# USB_Blaster.net
KiCad netlist of a schematic drawn in Altium Designer
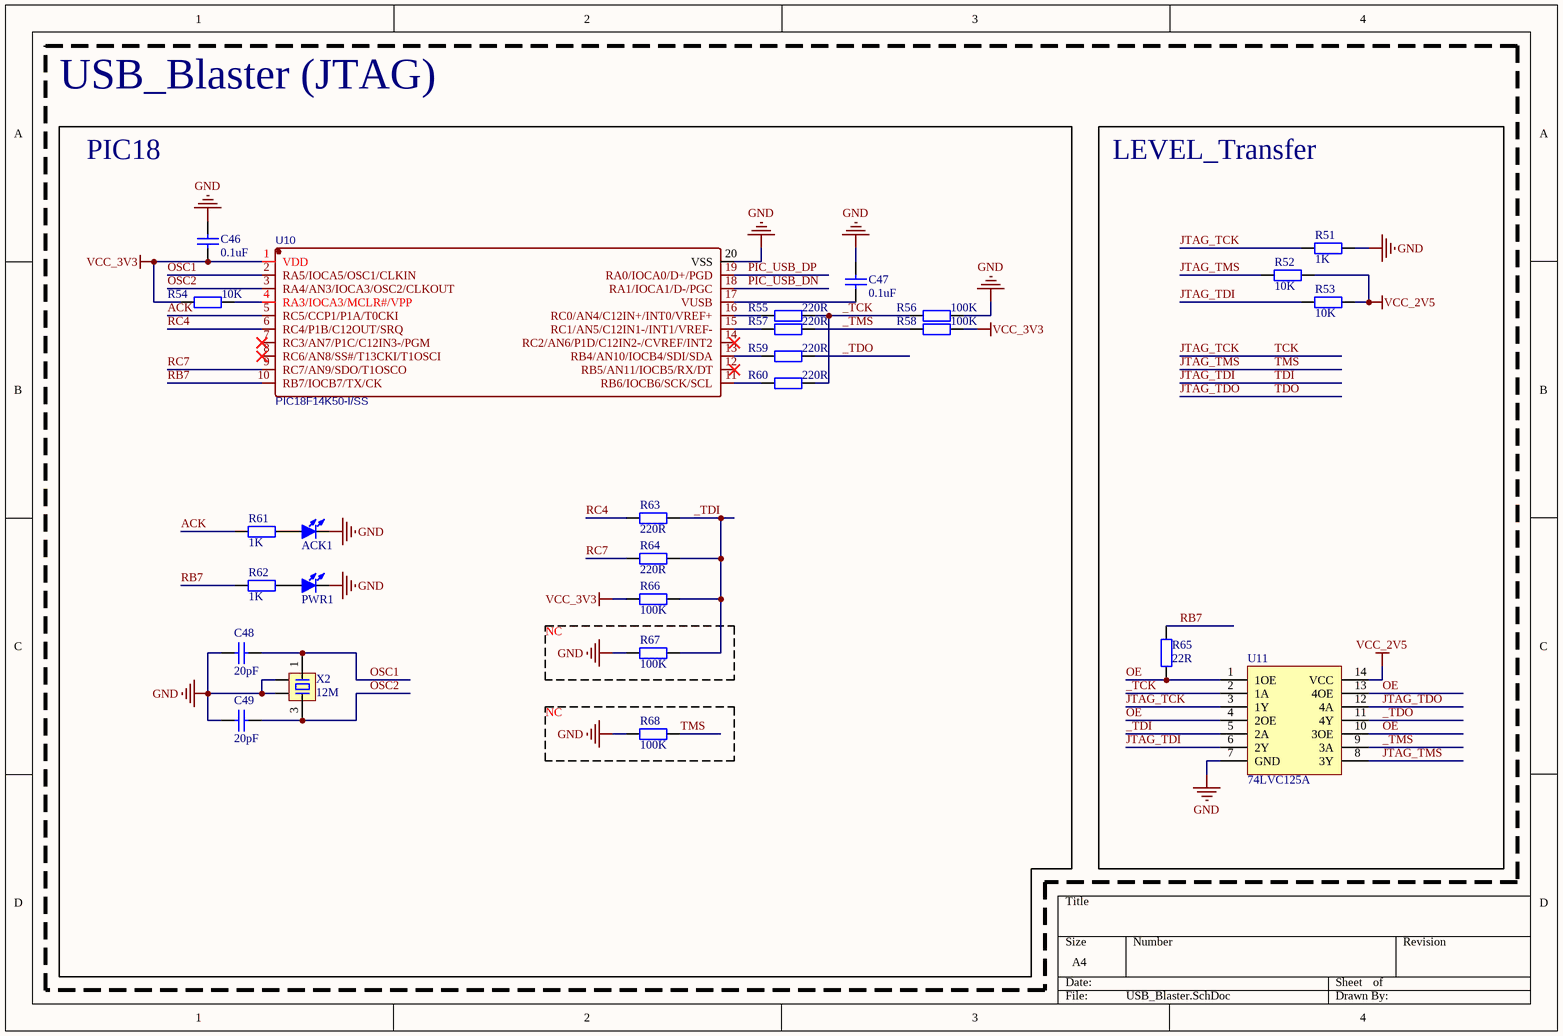
[diagram p0: USB_Blaster.SchDoc]

(export (version "E")
  (design (tool "Eeschema 10.0.6"))
  (components
    (comp (ref "ACK1")
      (value "红色")
      (footprint "LED 0603G")
      (description "贴片LED")
      (fields (field (name "版权归属") "源创客"))
      (libsource (lib "My_Devices") (part "0603_LED_G"))
    )
    (comp (ref "C46")
      (value "0.1uF")
      (footprint "0402_C")
      (description "贴片电容")
      (libsource (lib "My_Devices") (part "0402_C"))
    )
    (comp (ref "C47")
      (value "0.1uF")
      (footprint "0402_C")
      (description "贴片电容")
      (libsource (lib "My_Devices") (part "0402_C"))
    )
    (comp (ref "C48")
      (value "20pF")
      (footprint "0402_C")
      (description "贴片电容")
      (libsource (lib "My_Devices") (part "0402_C"))
    )
    (comp (ref "C49")
      (value "20pF")
      (footprint "0402_C")
      (description "贴片电容")
      (libsource (lib "My_Devices") (part "0402_C"))
    )
    (comp (ref "PWR1")
      (value "红色")
      (footprint "LED 0603R")
      (description "贴片LED")
      (fields (field (name "版权归属") "源创客"))
      (libsource (lib "My_Devices") (part "0603_LED_R"))
    )
    (comp (ref "R51")
      (value "1K")
      (footprint "0402_R")
      (description "贴片电阻")
      (libsource (lib "My_Devices") (part "0402_R"))
    )
    (comp (ref "R52")
      (value "10K")
      (footprint "0402_R")
      (description "贴片电阻")
      (libsource (lib "My_Devices") (part "0402_R"))
    )
    (comp (ref "R53")
      (value "10K")
      (footprint "0402_R")
      (description "贴片电阻")
      (libsource (lib "My_Devices") (part "0402_R"))
    )
    (comp (ref "R54")
      (value "10K")
      (footprint "0402_R")
      (description "贴片电阻")
      (libsource (lib "My_Devices") (part "0402_R"))
    )
    (comp (ref "R55")
      (value "220R")
      (footprint "0402_R")
      (description "贴片电阻")
      (libsource (lib "My_Devices") (part "0402_R"))
    )
    (comp (ref "R56")
      (value "100K")
      (footprint "0402_R")
      (description "贴片电阻")
      (libsource (lib "My_Devices") (part "0402_R"))
    )
    (comp (ref "R57")
      (value "220R")
      (footprint "0402_R")
      (description "贴片电阻")
      (libsource (lib "My_Devices") (part "0402_R"))
    )
    (comp (ref "R58")
      (value "100K")
      (footprint "0402_R")
      (description "贴片电阻")
      (libsource (lib "My_Devices") (part "0402_R"))
    )
    (comp (ref "R59")
      (value "220R")
      (footprint "0402_R")
      (description "贴片电阻")
      (libsource (lib "My_Devices") (part "0402_R"))
    )
    (comp (ref "R60")
      (value "220R")
      (footprint "0402_R")
      (description "贴片电阻")
      (libsource (lib "My_Devices") (part "0402_R"))
    )
    (comp (ref "R61")
      (value "1K")
      (footprint "0402_R")
      (description "贴片电阻")
      (libsource (lib "") (part "0402_R_1"))
    )
    (comp (ref "R62")
      (value "1K")
      (footprint "0402_R")
      (description "贴片电阻")
      (libsource (lib "") (part "0402_R_1"))
    )
    (comp (ref "R63")
      (value "220R")
      (footprint "0402_R")
      (description "贴片电阻")
      (libsource (lib "My_Devices") (part "0402_R"))
    )
    (comp (ref "R64")
      (value "220R")
      (footprint "0402_R")
      (description "贴片电阻")
      (libsource (lib "My_Devices") (part "0402_R"))
    )
    (comp (ref "R65")
      (value "22R")
      (footprint "0402_R")
      (description "贴片电阻")
      (libsource (lib "") (part "0402_R_2"))
    )
    (comp (ref "R66")
      (value "100K")
      (footprint "0402_R")
      (description "贴片电阻")
      (libsource (lib "") (part "0402_R_1"))
    )
    (comp (ref "R67")
      (value "100K")
      (footprint "0402_R")
      (description "贴片电阻")
      (libsource (lib "") (part "0402_R_1"))
    )
    (comp (ref "R68")
      (value "100K")
      (footprint "0402_R")
      (description "贴片电阻")
      (libsource (lib "") (part "0402_R_1"))
    )
    (comp (ref "U10")
      (value "PIC18F14K50-I/SS")
      (footprint "SSOP20_L")
      (fields (field (name "BOM_SUPPLIER PART") "C12460"))
      (libsource (lib "Schlib1") (part "PIC18F14K50-I/SS"))
    )
    (comp (ref "U11")
      (value "74LVC125A")
      (footprint "TSSOP14_N")
      (libsource (lib "Schlib1") (part "74LVC125A"))
    )
    (comp (ref "X2")
      (value "12M")
      (footprint "OSC 3225-4P")
      (description "4脚无源晶振")
      (fields (field (name "版权归属") "源创客"))
      (libsource (lib "My_Devices") (part "XTAL-4P"))
    )
  )
  (nets
    (net (code "1") (name "/ACK") (class "Default")
      (node (ref "R61") (pin "2") (pinfunction "2_2") (pintype "passive"))
      (node (ref "U10") (pin "5") (pinfunction "RC5/CCP1/P1A/T0CKI_5") (pintype "passive"))
    )
    (net (code "2") (name "/JTAG_TCK") (class "Default")
      (node (ref "R51") (pin "1") (pinfunction "1_1") (pintype "passive"))
      (node (ref "U11") (pin "3") (pinfunction "1Y_3") (pintype "passive"))
    )
    (net (code "3") (name "/JTAG_TDI") (class "Default")
      (node (ref "R53") (pin "1") (pinfunction "1_1") (pintype "passive"))
      (node (ref "U11") (pin "6") (pinfunction "2Y_6") (pintype "passive"))
    )
    (net (code "4") (name "/JTAG_TDO") (class "Default")
      (node (ref "U11") (pin "12") (pinfunction "4A_12") (pintype "passive"))
    )
    (net (code "5") (name "/JTAG_TMS") (class "Default")
      (node (ref "R52") (pin "1") (pinfunction "1_1") (pintype "passive"))
      (node (ref "R68") (pin "1") (pinfunction "1_1") (pintype "passive"))
      (node (ref "U11") (pin "8") (pinfunction "3Y_8") (pintype "passive"))
    )
    (net (code "6") (name "/OE") (class "Default")
      (node (ref "R65") (pin "1") (pinfunction "1_1") (pintype "passive"))
      (node (ref "U11") (pin "1") (pinfunction "1OE_1") (pintype "passive"))
      (node (ref "U11") (pin "10") (pinfunction "3OE_10") (pintype "passive"))
      (node (ref "U11") (pin "13") (pinfunction "4OE_13") (pintype "passive"))
      (node (ref "U11") (pin "4") (pinfunction "2OE_4") (pintype "passive"))
    )
    (net (code "7") (name "/OSC1") (class "Default")
      (node (ref "C48") (pin "2") (pinfunction "2_2") (pintype "passive"))
      (node (ref "U10") (pin "2") (pinfunction "RA5/IOCA5/OSC1/CLKIN_2") (pintype "passive"))
      (node (ref "X2") (pin "1") (pinfunction "1_1") (pintype "passive"))
    )
    (net (code "8") (name "/OSC2") (class "Default")
      (node (ref "C49") (pin "2") (pinfunction "2_2") (pintype "passive"))
      (node (ref "U10") (pin "3") (pinfunction "RA4/AN3/IOCA3/OSC2/CLKOUT_3") (pintype "passive"))
      (node (ref "X2") (pin "3") (pinfunction "3_3") (pintype "passive"))
    )
    (net (code "9") (name "/PIC_USB_DN") (class "Default")
      (node (ref "U10") (pin "18") (pinfunction "RA1/IOCA1/D-/PGC_18") (pintype "passive"))
    )
    (net (code "10") (name "/PIC_USB_DP") (class "Default")
      (node (ref "U10") (pin "19") (pinfunction "RA0/IOCA0/D+/PGD_19") (pintype "passive"))
    )
    (net (code "11") (name "/RB7") (class "Default")
      (node (ref "R62") (pin "2") (pinfunction "2_2") (pintype "passive"))
      (node (ref "R65") (pin "2") (pinfunction "2_2") (pintype "passive"))
      (node (ref "U10") (pin "10") (pinfunction "RB7/IOCB7/TX/CK_10") (pintype "passive"))
    )
    (net (code "12") (name "/RC4") (class "Default")
      (node (ref "R63") (pin "1") (pinfunction "1_1") (pintype "passive"))
      (node (ref "U10") (pin "6") (pinfunction "RC4/P1B/C12OUT/SRQ_6") (pintype "passive"))
    )
    (net (code "13") (name "/RC7") (class "Default")
      (node (ref "R64") (pin "1") (pinfunction "1_1") (pintype "passive"))
      (node (ref "U10") (pin "9") (pinfunction "RC7/AN9/SDO/T1OSCO_9") (pintype "passive"))
    )
    (net (code "14") (name "/_TCK") (class "Default")
      (node (ref "R55") (pin "2") (pinfunction "2_2") (pintype "passive"))
      (node (ref "R56") (pin "1") (pinfunction "1_1") (pintype "passive"))
      (node (ref "R60") (pin "2") (pinfunction "2_2") (pintype "passive"))
      (node (ref "U11") (pin "2") (pinfunction "1A_2") (pintype "passive"))
    )
    (net (code "15") (name "/_TDI") (class "Default")
      (node (ref "R63") (pin "2") (pinfunction "2_2") (pintype "passive"))
      (node (ref "R64") (pin "2") (pinfunction "2_2") (pintype "passive"))
      (node (ref "R66") (pin "1") (pinfunction "1_1") (pintype "passive"))
      (node (ref "R67") (pin "1") (pinfunction "1_1") (pintype "passive"))
      (node (ref "U11") (pin "5") (pinfunction "2A_5") (pintype "passive"))
    )
    (net (code "16") (name "/_TDO") (class "Default")
      (node (ref "R59") (pin "2") (pinfunction "2_2") (pintype "passive"))
      (node (ref "U11") (pin "11") (pinfunction "4Y_11") (pintype "passive"))
    )
    (net (code "17") (name "/_TMS") (class "Default")
      (node (ref "R57") (pin "2") (pinfunction "2_2") (pintype "passive"))
      (node (ref "R58") (pin "1") (pinfunction "1_1") (pintype "passive"))
      (node (ref "U11") (pin "9") (pinfunction "3A_9") (pintype "passive"))
    )
    (net (code "18") (name "GND") (class "Default")
      (node (ref "ACK1") (pin "2") (pinfunction "K_2") (pintype "passive"))
      (node (ref "C46") (pin "2") (pinfunction "2_2") (pintype "passive"))
      (node (ref "C47") (pin "1") (pinfunction "1_1") (pintype "passive"))
      (node (ref "C48") (pin "1") (pinfunction "1_1") (pintype "passive"))
      (node (ref "C49") (pin "1") (pinfunction "1_1") (pintype "passive"))
      (node (ref "PWR1") (pin "2") (pinfunction "K_2") (pintype "passive"))
      (node (ref "R51") (pin "2") (pinfunction "2_2") (pintype "passive"))
      (node (ref "R56") (pin "2") (pinfunction "2_2") (pintype "passive"))
      (node (ref "R67") (pin "2") (pinfunction "2_2") (pintype "passive"))
      (node (ref "R68") (pin "2") (pinfunction "2_2") (pintype "passive"))
      (node (ref "U10") (pin "20") (pinfunction "VSS_20") (pintype "passive"))
      (node (ref "U11") (pin "7") (pinfunction "GND_7") (pintype "passive"))
      (node (ref "X2") (pin "2") (pinfunction "2_2") (pintype "passive"))
      (node (ref "X2") (pin "4") (pinfunction "4_4") (pintype "passive"))
    )
    (net (code "19") (name "Net-(ACK1-A)") (class "Default")
      (node (ref "ACK1") (pin "1") (pinfunction "A_1") (pintype "passive"))
      (node (ref "R61") (pin "1") (pinfunction "1_1") (pintype "passive"))
    )
    (net (code "20") (name "Net-(PWR1-A)") (class "Default")
      (node (ref "PWR1") (pin "1") (pinfunction "A_1") (pintype "passive"))
      (node (ref "R62") (pin "1") (pinfunction "1_1") (pintype "passive"))
    )
    (net (code "21") (name "Net-(U10-RA3{slash}IOCA3{slash}MCLR#{slash}VPP)") (class "Default")
      (node (ref "R54") (pin "2") (pinfunction "2_2") (pintype "passive"))
      (node (ref "U10") (pin "4") (pinfunction "RA3/IOCA3/MCLR#/VPP_4") (pintype "passive"))
    )
    (net (code "22") (name "Net-(U10-RB4{slash}AN10{slash}IOCB4{slash}SDI{slash}SDA)") (class "Default")
      (node (ref "R59") (pin "1") (pinfunction "1_1") (pintype "passive"))
      (node (ref "U10") (pin "13") (pinfunction "RB4/AN10/IOCB4/SDI/SDA_13") (pintype "passive"))
    )
    (net (code "23") (name "Net-(U10-RB6{slash}IOCB6{slash}SCK{slash}SCL)") (class "Default")
      (node (ref "R60") (pin "1") (pinfunction "1_1") (pintype "passive"))
      (node (ref "U10") (pin "11") (pinfunction "RB6/IOCB6/SCK/SCL_11") (pintype "passive"))
    )
    (net (code "24") (name "Net-(U10-RC0{slash}AN4{slash}C12IN+{slash}INT0{slash}VREF+)") (class "Default")
      (node (ref "R55") (pin "1") (pinfunction "1_1") (pintype "passive"))
      (node (ref "U10") (pin "16") (pinfunction "RC0/AN4/C12IN+/INT0/VREF+_16") (pintype "passive"))
    )
    (net (code "25") (name "Net-(U10-RC1{slash}AN5{slash}C12IN1-{slash}INT1{slash}VREF-)") (class "Default")
      (node (ref "R57") (pin "1") (pinfunction "1_1") (pintype "passive"))
      (node (ref "U10") (pin "15") (pinfunction "RC1/AN5/C12IN1-/INT1/VREF-_15") (pintype "passive"))
    )
    (net (code "26") (name "Net-(U10-VUSB)") (class "Default")
      (node (ref "C47") (pin "2") (pinfunction "2_2") (pintype "passive"))
      (node (ref "U10") (pin "17") (pinfunction "VUSB_17") (pintype "passive"))
    )
    (net (code "27") (name "VCC_2V5") (class "Default")
      (node (ref "R52") (pin "2") (pinfunction "2_2") (pintype "passive"))
      (node (ref "R53") (pin "2") (pinfunction "2_2") (pintype "passive"))
      (node (ref "U11") (pin "14") (pinfunction "VCC_14") (pintype "passive"))
    )
    (net (code "28") (name "VCC_3V3") (class "Default")
      (node (ref "C46") (pin "1") (pinfunction "1_1") (pintype "passive"))
      (node (ref "R54") (pin "1") (pinfunction "1_1") (pintype "passive"))
      (node (ref "R58") (pin "2") (pinfunction "2_2") (pintype "passive"))
      (node (ref "R66") (pin "2") (pinfunction "2_2") (pintype "passive"))
      (node (ref "U10") (pin "1") (pinfunction "VDD_1") (pintype "passive"))
    )
    (net (code "29") (name "unconnected-(U10-RB5{slash}AN11{slash}IOCB5{slash}RX{slash}DT-Pad12)") (class "Default")
      (node (ref "U10") (pin "12") (pinfunction "RB5/AN11/IOCB5/RX/DT_12") (pintype "passive+no_connect"))
    )
    (net (code "30") (name "unconnected-(U10-RC2{slash}AN6{slash}P1D{slash}C12IN2-{slash}CVREF{slash}INT2-Pad14)") (class "Default")
      (node (ref "U10") (pin "14") (pinfunction "RC2/AN6/P1D/C12IN2-/CVREF/INT2_14") (pintype "passive+no_connect"))
    )
    (net (code "31") (name "unconnected-(U10-RC3{slash}AN7{slash}P1C{slash}C12IN3-{slash}PGM-Pad7)") (class "Default")
      (node (ref "U10") (pin "7") (pinfunction "RC3/AN7/P1C/C12IN3-/PGM_7") (pintype "passive+no_connect"))
    )
    (net (code "32") (name "unconnected-(U10-RC6{slash}AN8{slash}SS#{slash}T13CKI{slash}T1OSCI-Pad8)") (class "Default")
      (node (ref "U10") (pin "8") (pinfunction "RC6/AN8/SS#/T13CKI/T1OSCI_8") (pintype "passive+no_connect"))
    )
  )
)
